# lipo_charger.net
KiCad netlist of a schematic drawn in EAGLE
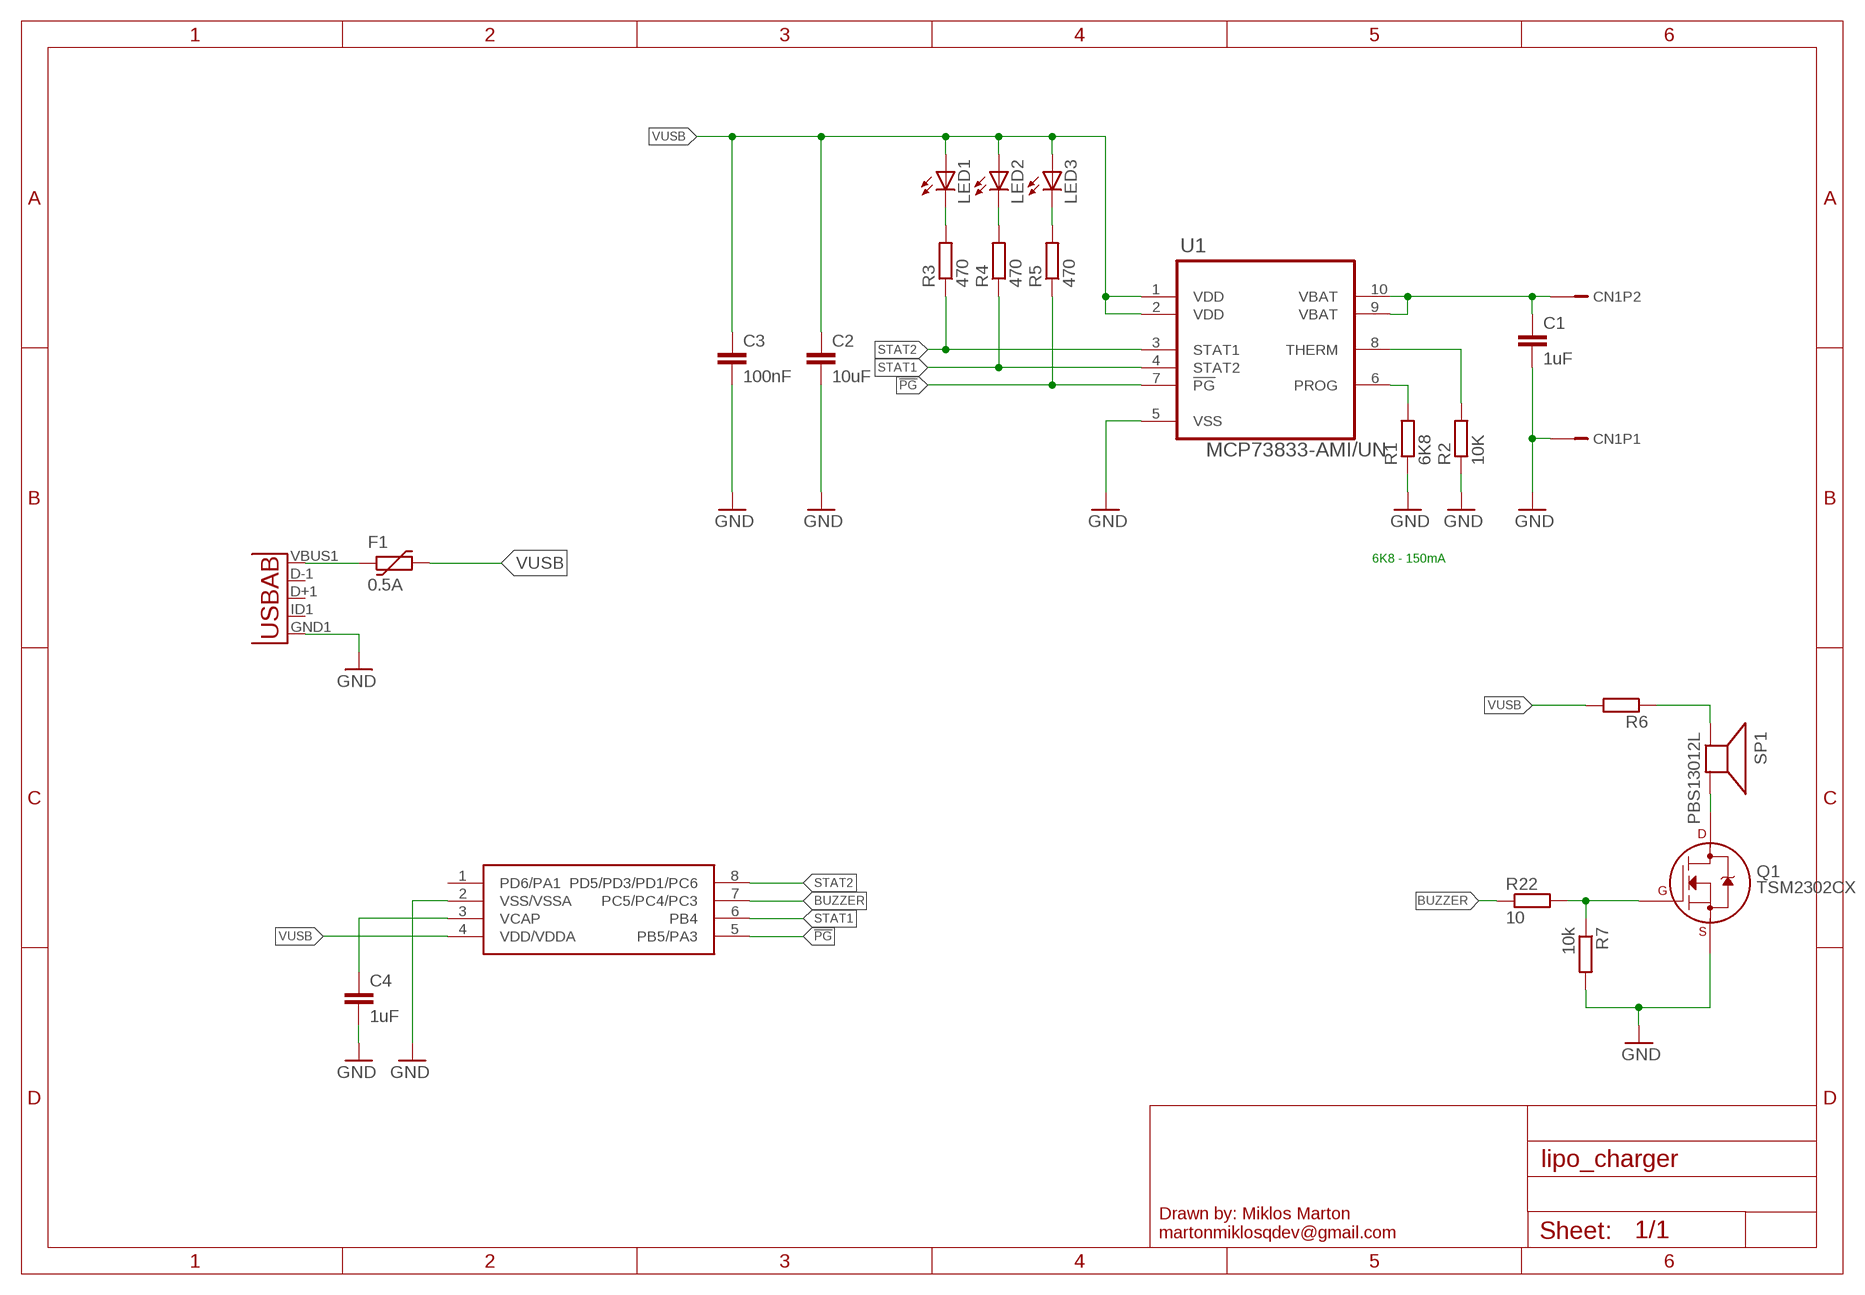
[diagram p0: schematic, sheet 1]

(export (version "E")
  (design (tool "Eeschema 10.0.6"))
  (components
    (comp (ref "C1")
      (value "1uF")
      (footprint "eagle-import:C0805")
      (libsource (lib "eagle-import") (part "C-EUC0805"))
    )
    (comp (ref "C2")
      (value "10uF")
      (footprint "eagle-import:C0805")
      (libsource (lib "eagle-import") (part "C-EUC0805"))
    )
    (comp (ref "C3")
      (value "100nF")
      (footprint "eagle-import:C0603")
      (libsource (lib "eagle-import") (part "C-EUC0603"))
    )
    (comp (ref "C4")
      (value "1uF")
      (footprint "eagle-import:C0603")
      (libsource (lib "eagle-import") (part "C-EUC0603"))
    )
    (comp (ref "CN1")
      (value "B2B-PH-K-S")
      (footprint "eagle-import:B2B-PH-K-S")
      (libsource (lib "eagle-import") (part "B2B-PH-K-S"))
    )
    (comp (ref "F1")
      (value "0.5A")
      (footprint "eagle-import:PTC0805")
      (libsource (lib "eagle-import") (part "FUSE_PTC-0805"))
    )
    (comp (ref "LED1")
      (value "LED0603")
      (footprint "eagle-import:CHIPLED_0603")
      (libsource (lib "eagle-import") (part "LED0603"))
    )
    (comp (ref "LED2")
      (value "LED0603")
      (footprint "eagle-import:CHIPLED_0603")
      (libsource (lib "eagle-import") (part "LED0603"))
    )
    (comp (ref "LED3")
      (value "LED0603")
      (footprint "eagle-import:CHIPLED_0603")
      (libsource (lib "eagle-import") (part "LED0603"))
    )
    (comp (ref "Q1")
      (value "TSM2302CX")
      (footprint "eagle-import:SOT-23")
      (libsource (lib "eagle-import") (part "2N700_SOT232A"))
    )
    (comp (ref "R1")
      (value "6K8")
      (footprint "eagle-import:R0603")
      (libsource (lib "eagle-import") (part "R-EU_R0603"))
    )
    (comp (ref "R2")
      (value "10K")
      (footprint "eagle-import:R0603")
      (libsource (lib "eagle-import") (part "R-EU_R0603"))
    )
    (comp (ref "R3")
      (value "470")
      (footprint "eagle-import:R0603")
      (libsource (lib "eagle-import") (part "R-EU_R0603"))
    )
    (comp (ref "R4")
      (value "470")
      (footprint "eagle-import:R0603")
      (libsource (lib "eagle-import") (part "R-EU_R0603"))
    )
    (comp (ref "R5")
      (value "470")
      (footprint "eagle-import:R0603")
      (libsource (lib "eagle-import") (part "R-EU_R0603"))
    )
    (comp (ref "R6")
      (value "R-EU_R0603")
      (footprint "eagle-import:R0603")
      (libsource (lib "eagle-import") (part "R-EU_R0603"))
    )
    (comp (ref "R7")
      (value "10k")
      (footprint "eagle-import:R0603")
      (libsource (lib "eagle-import") (part "R-EU_R0603"))
    )
    (comp (ref "R22")
      (value "10")
      (footprint "eagle-import:R0603")
      (libsource (lib "eagle-import") (part "R-EU_R0603"))
    )
    (comp (ref "SP1")
      (value "PBS13012L")
      (footprint "eagle-import:AL60P")
      (libsource (lib "eagle-import") (part "SPEAKER/AL60P"))
    )
    (comp (ref "U1")
      (value "MCP73833-AMI/UN")
      (footprint "eagle-import:SOP50P490X110-10N")
      (libsource (lib "eagle-import") (part "MCP73833-AMI/UN"))
    )
    (comp (ref "U2")
      (value "STM8S001J3")
      (footprint "eagle-import:SO8N")
      (libsource (lib "eagle-import") (part "STM8S001J3"))
    )
    (comp (ref "X1")
      (value "USB-ABIN&OUT")
      (footprint "eagle-import:USB-AB-MICRO-SMD-V03-IN&OUT")
      (libsource (lib "eagle-import") (part "USB-ABIN&OUT"))
    )
  )
  (nets
    (net (code "1") (name "/~{PG}") (class "Default")
      (node (ref "R5") (pin "1") (pinfunction "1_1") (pintype "passive"))
      (node (ref "U1") (pin "7") (pinfunction "~{PG}_7") (pintype "open_collector"))
      (node (ref "U2") (pin "5") (pinfunction "PB5/PA3_5") (pintype "bidirectional"))
    )
    (net (code "2") (name "BUZZER") (class "Default")
      (node (ref "R22") (pin "1") (pinfunction "1_1") (pintype "passive"))
      (node (ref "U2") (pin "7") (pinfunction "PC5/PC4/PC3_7") (pintype "bidirectional"))
    )
    (net (code "3") (name "GND") (class "Default")
      (node (ref "C1") (pin "2") (pinfunction "2_2") (pintype "passive"))
      (node (ref "C2") (pin "2") (pinfunction "2_2") (pintype "passive"))
      (node (ref "C3") (pin "2") (pinfunction "2_2") (pintype "passive"))
      (node (ref "C4") (pin "2") (pinfunction "2_2") (pintype "passive"))
      (node (ref "CN1") (pin "1") (pinfunction "1_1") (pintype "passive"))
      (node (ref "Q1") (pin "2") (pinfunction "S_2") (pintype "bidirectional"))
      (node (ref "R1") (pin "1") (pinfunction "1_1") (pintype "passive"))
      (node (ref "R2") (pin "1") (pinfunction "1_1") (pintype "passive"))
      (node (ref "R7") (pin "2") (pinfunction "2_2") (pintype "passive"))
      (node (ref "U1") (pin "5") (pinfunction "VSS_5") (pintype "passive"))
      (node (ref "U2") (pin "2") (pinfunction "VSS/VSSA_2") (pintype "passive"))
      (node (ref "X1") (pin "GND1") (pinfunction "GND_GND1") (pintype "bidirectional"))
    )
    (net (code "4") (name "Net-(CN1B-1)") (class "Default")
      (node (ref "C1") (pin "1") (pinfunction "1_1") (pintype "passive"))
      (node (ref "CN1") (pin "2") (pinfunction "1_2") (pintype "passive"))
      (node (ref "U1") (pin "10") (pinfunction "VBAT_10") (pintype "output"))
      (node (ref "U1") (pin "9") (pinfunction "VBAT_9") (pintype "output"))
    )
    (net (code "5") (name "Net-(LED1-PadC)") (class "Default")
      (node (ref "LED1") (pin "C") (pinfunction "C_C") (pintype "passive"))
      (node (ref "R3") (pin "2") (pinfunction "2_2") (pintype "passive"))
    )
    (net (code "6") (name "Net-(LED2-PadC)") (class "Default")
      (node (ref "LED2") (pin "C") (pinfunction "C_C") (pintype "passive"))
      (node (ref "R4") (pin "2") (pinfunction "2_2") (pintype "passive"))
    )
    (net (code "7") (name "Net-(LED3-PadC)") (class "Default")
      (node (ref "LED3") (pin "C") (pinfunction "C_C") (pintype "passive"))
      (node (ref "R5") (pin "2") (pinfunction "2_2") (pintype "passive"))
    )
    (net (code "8") (name "Net-(Q1-D)") (class "Default")
      (node (ref "Q1") (pin "3") (pinfunction "D_3") (pintype "bidirectional"))
      (node (ref "SP1") (pin "2") (pinfunction "-_2") (pintype "passive"))
    )
    (net (code "9") (name "Net-(Q1-G)") (class "Default")
      (node (ref "Q1") (pin "1") (pinfunction "G_1") (pintype "tri_state"))
      (node (ref "R22") (pin "2") (pinfunction "2_2") (pintype "passive"))
      (node (ref "R7") (pin "1") (pinfunction "1_1") (pintype "passive"))
    )
    (net (code "10") (name "Net-(SP1-+)") (class "Default")
      (node (ref "R6") (pin "1") (pinfunction "1_1") (pintype "passive"))
      (node (ref "SP1") (pin "1") (pinfunction "+_1") (pintype "passive"))
    )
    (net (code "11") (name "Net-(U1-PROG)") (class "Default")
      (node (ref "R1") (pin "2") (pinfunction "2_2") (pintype "passive"))
      (node (ref "U1") (pin "6") (pinfunction "PROG_6") (pintype "input"))
    )
    (net (code "12") (name "Net-(U1-THERM)") (class "Default")
      (node (ref "R2") (pin "2") (pinfunction "2_2") (pintype "passive"))
      (node (ref "U1") (pin "8") (pinfunction "THERM_8") (pintype "input"))
    )
    (net (code "13") (name "Net-(U2-VCAP)") (class "Default")
      (node (ref "C4") (pin "1") (pinfunction "1_1") (pintype "passive"))
      (node (ref "U2") (pin "3") (pinfunction "VCAP_3") (pintype "bidirectional"))
    )
    (net (code "14") (name "Net-(X1-VBUS)") (class "Default")
      (node (ref "F1") (pin "1") (pinfunction "1_1") (pintype "passive"))
      (node (ref "X1") (pin "VBUS1") (pinfunction "VBUS_VBUS1") (pintype "bidirectional"))
    )
    (net (code "15") (name "STAT1") (class "Default")
      (node (ref "R4") (pin "1") (pinfunction "1_1") (pintype "passive"))
      (node (ref "U1") (pin "4") (pinfunction "STAT2_4") (pintype "open_collector"))
      (node (ref "U2") (pin "6") (pinfunction "PB4_6") (pintype "bidirectional"))
    )
    (net (code "16") (name "STAT2") (class "Default")
      (node (ref "R3") (pin "1") (pinfunction "1_1") (pintype "passive"))
      (node (ref "U1") (pin "3") (pinfunction "STAT1_3") (pintype "open_collector"))
      (node (ref "U2") (pin "8") (pinfunction "PD5/PD3/PD1/PC6_8") (pintype "bidirectional"))
    )
    (net (code "17") (name "VUSB") (class "Default")
      (node (ref "C2") (pin "1") (pinfunction "1_1") (pintype "passive"))
      (node (ref "C3") (pin "1") (pinfunction "1_1") (pintype "passive"))
      (node (ref "F1") (pin "2") (pinfunction "2_2") (pintype "passive"))
      (node (ref "LED1") (pin "A") (pinfunction "A_A") (pintype "passive"))
      (node (ref "LED2") (pin "A") (pinfunction "A_A") (pintype "passive"))
      (node (ref "LED3") (pin "A") (pinfunction "A_A") (pintype "passive"))
      (node (ref "R6") (pin "2") (pinfunction "2_2") (pintype "passive"))
      (node (ref "U1") (pin "1") (pinfunction "VDD_1") (pintype "power_in"))
      (node (ref "U1") (pin "2") (pinfunction "VDD_2") (pintype "power_in"))
      (node (ref "U2") (pin "4") (pinfunction "VDD/VDDA_4") (pintype "passive"))
    )
    (net (code "18") (name "unconnected-(U2-PD6{slash}PA1-Pad1)") (class "Default")
      (node (ref "U2") (pin "1") (pinfunction "PD6/PA1_1") (pintype "bidirectional"))
    )
    (net (code "19") (name "unconnected-(X1-D+-PadD+1)") (class "Default")
      (node (ref "X1") (pin "D+1") (pinfunction "D+_D+1") (pintype "bidirectional"))
    )
    (net (code "20") (name "unconnected-(X1-D--PadD-1)") (class "Default")
      (node (ref "X1") (pin "D-1") (pinfunction "D-_D-1") (pintype "bidirectional"))
    )
    (net (code "21") (name "unconnected-(X1-USBID-PadID1)") (class "Default")
      (node (ref "X1") (pin "ID1") (pinfunction "USBID_ID1") (pintype "bidirectional"))
    )
  )
)
